# SensorPCBA_v0_2.net
KiCad netlist of a schematic drawn in Altium Designer
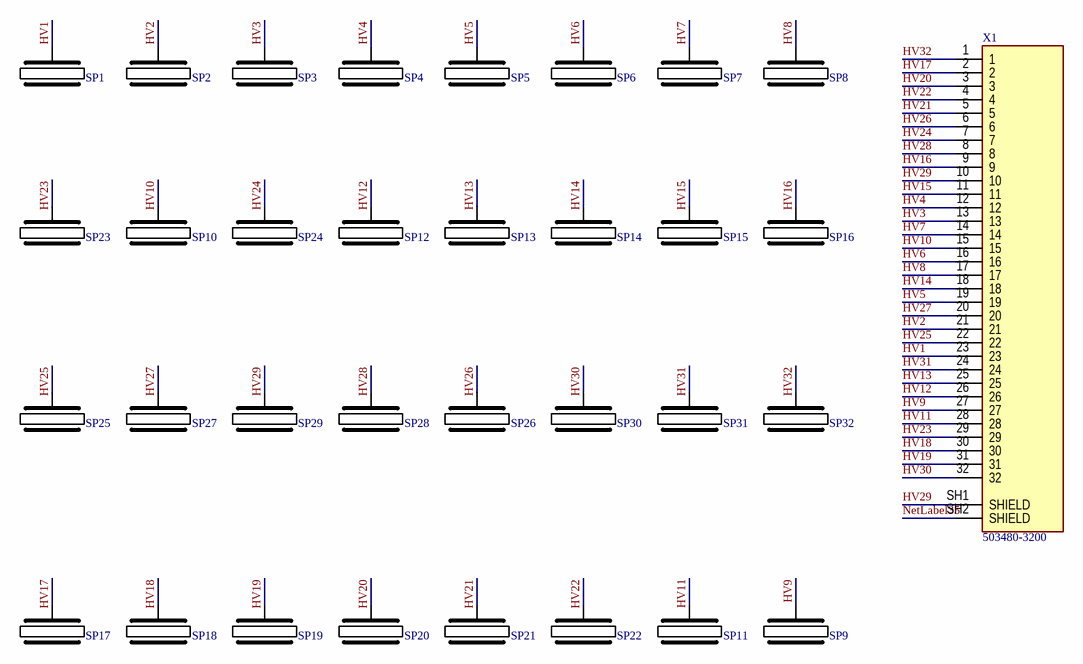
[diagram p0: SensorPCBA_v0.2.SchDoc]

(export (version "E")
  (design (tool "Eeschema 10.0.6"))
  (components
    (comp (ref "SP1")
      (value "SensorPAD")
      (footprint "Pump_via")
      (libsource (lib "SensorPCBA") (part "SensorPAD"))
    )
    (comp (ref "SP2")
      (value "SensorPAD")
      (footprint "Pump_via")
      (libsource (lib "SensorPCBA") (part "SensorPAD"))
    )
    (comp (ref "SP3")
      (value "SensorPAD")
      (footprint "Pump_via")
      (libsource (lib "SensorPCBA") (part "SensorPAD"))
    )
    (comp (ref "SP4")
      (value "SensorPAD")
      (footprint "Pump_via")
      (libsource (lib "SensorPCBA") (part "SensorPAD"))
    )
    (comp (ref "SP5")
      (value "SensorPAD")
      (footprint "Pump_via")
      (libsource (lib "SensorPCBA") (part "SensorPAD"))
    )
    (comp (ref "SP6")
      (value "SensorPAD")
      (footprint "Pump_via")
      (libsource (lib "SensorPCBA") (part "SensorPAD"))
    )
    (comp (ref "SP7")
      (value "SensorPAD")
      (footprint "Pump_via")
      (libsource (lib "SensorPCBA") (part "SensorPAD"))
    )
    (comp (ref "SP8")
      (value "SensorPAD")
      (footprint "Pump_via")
      (libsource (lib "SensorPCBA") (part "SensorPAD"))
    )
    (comp (ref "SP9")
      (value "SensorPAD")
      (footprint "Pump_via")
      (libsource (lib "SensorPCBA") (part "SensorPAD"))
    )
    (comp (ref "SP10")
      (value "SensorPAD")
      (footprint "Pump_via")
      (libsource (lib "SensorPCBA") (part "SensorPAD"))
    )
    (comp (ref "SP11")
      (value "SensorPAD")
      (footprint "Pump_via")
      (libsource (lib "SensorPCBA") (part "SensorPAD"))
    )
    (comp (ref "SP12")
      (value "SensorPAD")
      (footprint "Pump_via")
      (libsource (lib "SensorPCBA") (part "SensorPAD"))
    )
    (comp (ref "SP13")
      (value "SensorPAD")
      (footprint "Pump_via")
      (libsource (lib "SensorPCBA") (part "SensorPAD"))
    )
    (comp (ref "SP14")
      (value "SensorPAD")
      (footprint "Pump_via")
      (libsource (lib "SensorPCBA") (part "SensorPAD"))
    )
    (comp (ref "SP15")
      (value "SensorPAD")
      (footprint "Pump_via")
      (libsource (lib "SensorPCBA") (part "SensorPAD"))
    )
    (comp (ref "SP16")
      (value "SensorPAD")
      (footprint "Pump_via")
      (libsource (lib "SensorPCBA") (part "SensorPAD"))
    )
    (comp (ref "SP17")
      (value "SensorPAD")
      (footprint "Pump_via")
      (libsource (lib "SensorPCBA") (part "SensorPAD"))
    )
    (comp (ref "SP18")
      (value "SensorPAD")
      (footprint "Pump_via")
      (libsource (lib "SensorPCBA") (part "SensorPAD"))
    )
    (comp (ref "SP19")
      (value "SensorPAD")
      (footprint "Pump_via")
      (libsource (lib "SensorPCBA") (part "SensorPAD"))
    )
    (comp (ref "SP20")
      (value "SensorPAD")
      (footprint "Pump_via")
      (libsource (lib "SensorPCBA") (part "SensorPAD"))
    )
    (comp (ref "SP21")
      (value "SensorPAD")
      (footprint "Pump_via")
      (libsource (lib "SensorPCBA") (part "SensorPAD"))
    )
    (comp (ref "SP22")
      (value "SensorPAD")
      (footprint "Pump_via")
      (libsource (lib "SensorPCBA") (part "SensorPAD"))
    )
    (comp (ref "SP23")
      (value "SensorPAD")
      (footprint "Pump_via")
      (libsource (lib "SensorPCBA") (part "SensorPAD"))
    )
    (comp (ref "SP24")
      (value "SensorPAD")
      (footprint "Pump_via")
      (libsource (lib "SensorPCBA") (part "SensorPAD"))
    )
    (comp (ref "SP25")
      (value "SensorPAD")
      (footprint "Pump_via")
      (libsource (lib "SensorPCBA") (part "SensorPAD"))
    )
    (comp (ref "SP26")
      (value "SensorPAD")
      (footprint "Pump_via")
      (libsource (lib "SensorPCBA") (part "SensorPAD"))
    )
    (comp (ref "SP27")
      (value "SensorPAD")
      (footprint "Pump_via")
      (libsource (lib "SensorPCBA") (part "SensorPAD"))
    )
    (comp (ref "SP28")
      (value "SensorPAD")
      (footprint "Pump_via")
      (libsource (lib "SensorPCBA") (part "SensorPAD"))
    )
    (comp (ref "SP29")
      (value "SensorPAD")
      (footprint "Pump_via")
      (libsource (lib "SensorPCBA") (part "SensorPAD"))
    )
    (comp (ref "SP30")
      (value "SensorPAD")
      (footprint "Pump_via")
      (libsource (lib "SensorPCBA") (part "SensorPAD"))
    )
    (comp (ref "SP31")
      (value "SensorPAD")
      (footprint "Pump_via")
      (libsource (lib "SensorPCBA") (part "SensorPAD"))
    )
    (comp (ref "SP32")
      (value "SensorPAD")
      (footprint "Pump_via")
      (libsource (lib "SensorPCBA") (part "SensorPAD"))
    )
    (comp (ref "X1")
      (value "503480-3200")
      (footprint "MOLEX_503480-3200")
      (description "32 Position FFC, FPC Connector Contacts, Top and Bottom 0.020 (0.50mm) Surface Mount, Right Angle")
      (fields (field (name "MF") "Molex") (field (name "MP") "5034803200"))
      (libsource (lib "SensorPCBA") (part "503480-3200"))
    )
  )
  (nets
    (net (code "1") (name "/HV1") (class "Default")
      (node (ref "SP1") (pin "1") (pinfunction "Atop_1") (pintype "passive"))
      (node (ref "X1") (pin "23") (pinfunction "23_23") (pintype "passive"))
    )
    (net (code "2") (name "/HV2") (class "Default")
      (node (ref "SP2") (pin "1") (pinfunction "Atop_1") (pintype "passive"))
      (node (ref "X1") (pin "21") (pinfunction "21_21") (pintype "passive"))
    )
    (net (code "3") (name "/HV3") (class "Default")
      (node (ref "SP3") (pin "1") (pinfunction "Atop_1") (pintype "passive"))
      (node (ref "X1") (pin "13") (pinfunction "13_13") (pintype "passive"))
    )
    (net (code "4") (name "/HV4") (class "Default")
      (node (ref "SP4") (pin "1") (pinfunction "Atop_1") (pintype "passive"))
      (node (ref "X1") (pin "12") (pinfunction "12_12") (pintype "passive"))
    )
    (net (code "5") (name "/HV5") (class "Default")
      (node (ref "SP5") (pin "1") (pinfunction "Atop_1") (pintype "passive"))
      (node (ref "X1") (pin "19") (pinfunction "19_19") (pintype "passive"))
    )
    (net (code "6") (name "/HV6") (class "Default")
      (node (ref "SP6") (pin "1") (pinfunction "Atop_1") (pintype "passive"))
      (node (ref "X1") (pin "16") (pinfunction "16_16") (pintype "passive"))
    )
    (net (code "7") (name "/HV7") (class "Default")
      (node (ref "SP7") (pin "1") (pinfunction "Atop_1") (pintype "passive"))
      (node (ref "X1") (pin "14") (pinfunction "14_14") (pintype "passive"))
    )
    (net (code "8") (name "/HV8") (class "Default")
      (node (ref "SP8") (pin "1") (pinfunction "Atop_1") (pintype "passive"))
      (node (ref "X1") (pin "17") (pinfunction "17_17") (pintype "passive"))
    )
    (net (code "9") (name "/HV9") (class "Default")
      (node (ref "SP9") (pin "1") (pinfunction "Atop_1") (pintype "passive"))
      (node (ref "X1") (pin "27") (pinfunction "27_27") (pintype "passive"))
    )
    (net (code "10") (name "/HV10") (class "Default")
      (node (ref "SP10") (pin "1") (pinfunction "Atop_1") (pintype "passive"))
      (node (ref "X1") (pin "15") (pinfunction "15_15") (pintype "passive"))
    )
    (net (code "11") (name "/HV11") (class "Default")
      (node (ref "SP11") (pin "1") (pinfunction "Atop_1") (pintype "passive"))
      (node (ref "X1") (pin "28") (pinfunction "28_28") (pintype "passive"))
    )
    (net (code "12") (name "/HV12") (class "Default")
      (node (ref "SP12") (pin "1") (pinfunction "Atop_1") (pintype "passive"))
      (node (ref "X1") (pin "26") (pinfunction "26_26") (pintype "passive"))
    )
    (net (code "13") (name "/HV13") (class "Default")
      (node (ref "SP13") (pin "1") (pinfunction "Atop_1") (pintype "passive"))
      (node (ref "X1") (pin "25") (pinfunction "25_25") (pintype "passive"))
    )
    (net (code "14") (name "/HV14") (class "Default")
      (node (ref "SP14") (pin "1") (pinfunction "Atop_1") (pintype "passive"))
      (node (ref "X1") (pin "18") (pinfunction "18_18") (pintype "passive"))
    )
    (net (code "15") (name "/HV15") (class "Default")
      (node (ref "SP15") (pin "1") (pinfunction "Atop_1") (pintype "passive"))
      (node (ref "X1") (pin "11") (pinfunction "11_11") (pintype "passive"))
    )
    (net (code "16") (name "/HV16") (class "Default")
      (node (ref "SP16") (pin "1") (pinfunction "Atop_1") (pintype "passive"))
      (node (ref "X1") (pin "9") (pinfunction "9_9") (pintype "passive"))
    )
    (net (code "17") (name "/HV17") (class "Default")
      (node (ref "SP17") (pin "1") (pinfunction "Atop_1") (pintype "passive"))
      (node (ref "X1") (pin "2") (pinfunction "2_2") (pintype "passive"))
    )
    (net (code "18") (name "/HV18") (class "Default")
      (node (ref "SP18") (pin "1") (pinfunction "Atop_1") (pintype "passive"))
      (node (ref "X1") (pin "30") (pinfunction "30_30") (pintype "passive"))
    )
    (net (code "19") (name "/HV19") (class "Default")
      (node (ref "SP19") (pin "1") (pinfunction "Atop_1") (pintype "passive"))
      (node (ref "X1") (pin "31") (pinfunction "31_31") (pintype "passive"))
    )
    (net (code "20") (name "/HV20") (class "Default")
      (node (ref "SP20") (pin "1") (pinfunction "Atop_1") (pintype "passive"))
      (node (ref "X1") (pin "3") (pinfunction "3_3") (pintype "passive"))
    )
    (net (code "21") (name "/HV21") (class "Default")
      (node (ref "SP21") (pin "1") (pinfunction "Atop_1") (pintype "passive"))
      (node (ref "X1") (pin "5") (pinfunction "5_5") (pintype "passive"))
    )
    (net (code "22") (name "/HV22") (class "Default")
      (node (ref "SP22") (pin "1") (pinfunction "Atop_1") (pintype "passive"))
      (node (ref "X1") (pin "4") (pinfunction "4_4") (pintype "passive"))
    )
    (net (code "23") (name "/HV23") (class "Default")
      (node (ref "SP23") (pin "1") (pinfunction "Atop_1") (pintype "passive"))
      (node (ref "X1") (pin "29") (pinfunction "29_29") (pintype "passive"))
    )
    (net (code "24") (name "/HV24") (class "Default")
      (node (ref "SP24") (pin "1") (pinfunction "Atop_1") (pintype "passive"))
      (node (ref "X1") (pin "7") (pinfunction "7_7") (pintype "passive"))
    )
    (net (code "25") (name "/HV25") (class "Default")
      (node (ref "SP25") (pin "1") (pinfunction "Atop_1") (pintype "passive"))
      (node (ref "X1") (pin "22") (pinfunction "22_22") (pintype "passive"))
    )
    (net (code "26") (name "/HV26") (class "Default")
      (node (ref "SP26") (pin "1") (pinfunction "Atop_1") (pintype "passive"))
      (node (ref "X1") (pin "6") (pinfunction "6_6") (pintype "passive"))
    )
    (net (code "27") (name "/HV27") (class "Default")
      (node (ref "SP27") (pin "1") (pinfunction "Atop_1") (pintype "passive"))
      (node (ref "X1") (pin "20") (pinfunction "20_20") (pintype "passive"))
    )
    (net (code "28") (name "/HV28") (class "Default")
      (node (ref "SP28") (pin "1") (pinfunction "Atop_1") (pintype "passive"))
      (node (ref "X1") (pin "8") (pinfunction "8_8") (pintype "passive"))
    )
    (net (code "29") (name "/HV29") (class "Default")
      (node (ref "SP29") (pin "1") (pinfunction "Atop_1") (pintype "passive"))
      (node (ref "X1") (pin "10") (pinfunction "10_10") (pintype "passive"))
      (node (ref "X1") (pin "SH1") (pinfunction "SHIELD_SH1") (pintype "passive"))
    )
    (net (code "30") (name "/HV30") (class "Default")
      (node (ref "SP30") (pin "1") (pinfunction "Atop_1") (pintype "passive"))
      (node (ref "X1") (pin "32") (pinfunction "32_32") (pintype "passive"))
    )
    (net (code "31") (name "/HV31") (class "Default")
      (node (ref "SP31") (pin "1") (pinfunction "Atop_1") (pintype "passive"))
      (node (ref "X1") (pin "24") (pinfunction "24_24") (pintype "passive"))
    )
    (net (code "32") (name "/HV32") (class "Default")
      (node (ref "SP32") (pin "1") (pinfunction "Atop_1") (pintype "passive"))
      (node (ref "X1") (pin "1") (pinfunction "1_1") (pintype "passive"))
    )
    (net (code "33") (name "/NetLabel35") (class "Default")
      (node (ref "X1") (pin "SH2") (pinfunction "SHIELD_SH2") (pintype "passive"))
    )
  )
)
